# mechanical.net
KiCad netlist of a schematic drawn in Altium Designer
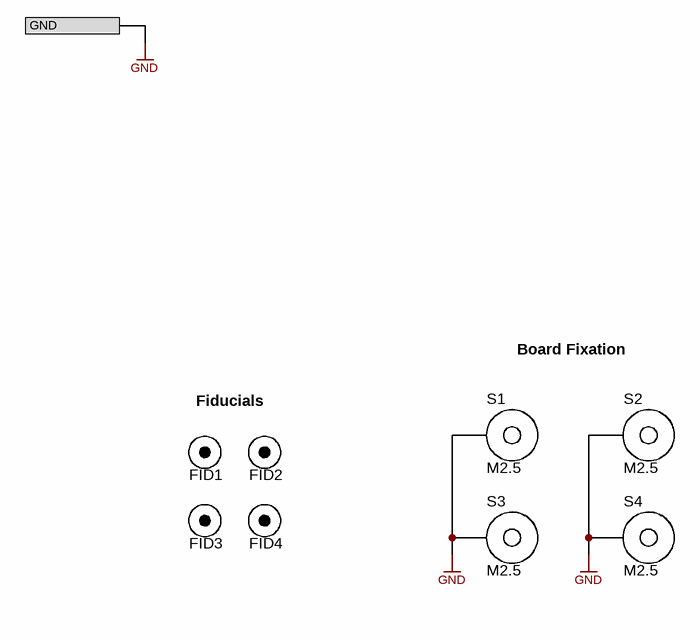
[diagram p0: mechanical.SchDoc]

(export (version "E")
  (design (tool "Eeschema 10.0.6"))
  (components
    (comp (ref "FID1")
      (value "Fiducial 1.5 mm")
      (footprint "FIDUCIAL")
      (libsource (lib "motionboard") (part "FIDUCIAL"))
    )
    (comp (ref "FID2")
      (value "Fiducial 1.5 mm")
      (footprint "FIDUCIAL")
      (libsource (lib "motionboard") (part "FIDUCIAL"))
    )
    (comp (ref "FID3")
      (value "Fiducial 1.5 mm")
      (footprint "FIDUCIAL")
      (libsource (lib "motionboard") (part "FIDUCIAL"))
    )
    (comp (ref "FID4")
      (value "Fiducial 1.5 mm")
      (footprint "FIDUCIAL")
      (libsource (lib "motionboard") (part "FIDUCIAL"))
    )
    (comp (ref "S1")
      (value "M2.5")
      (footprint "HW/HOLE/M2.5/VIA")
      (libsource (lib "motionboard") (part "HOLE/M2.5"))
    )
    (comp (ref "S2")
      (value "M2.5")
      (footprint "HW/HOLE/M2.5/VIA")
      (libsource (lib "motionboard") (part "HOLE/M2.5"))
    )
    (comp (ref "S3")
      (value "M2.5")
      (footprint "HW/HOLE/M2.5/VIA")
      (libsource (lib "motionboard") (part "HOLE/M2.5"))
    )
    (comp (ref "S4")
      (value "M2.5")
      (footprint "HW/HOLE/M2.5/VIA")
      (libsource (lib "motionboard") (part "HOLE/M2.5"))
    )
  )
  (nets
    (net (code "1") (name "GND") (class "Default")
      (node (ref "S1") (pin "1") (pinfunction "1_1") (pintype "passive"))
      (node (ref "S2") (pin "1") (pinfunction "1_1") (pintype "passive"))
      (node (ref "S3") (pin "1") (pinfunction "1_1") (pintype "passive"))
      (node (ref "S4") (pin "1") (pinfunction "1_1") (pintype "passive"))
    )
  )
)
